# HW2.net
KiCad netlist of a schematic drawn in EAGLE
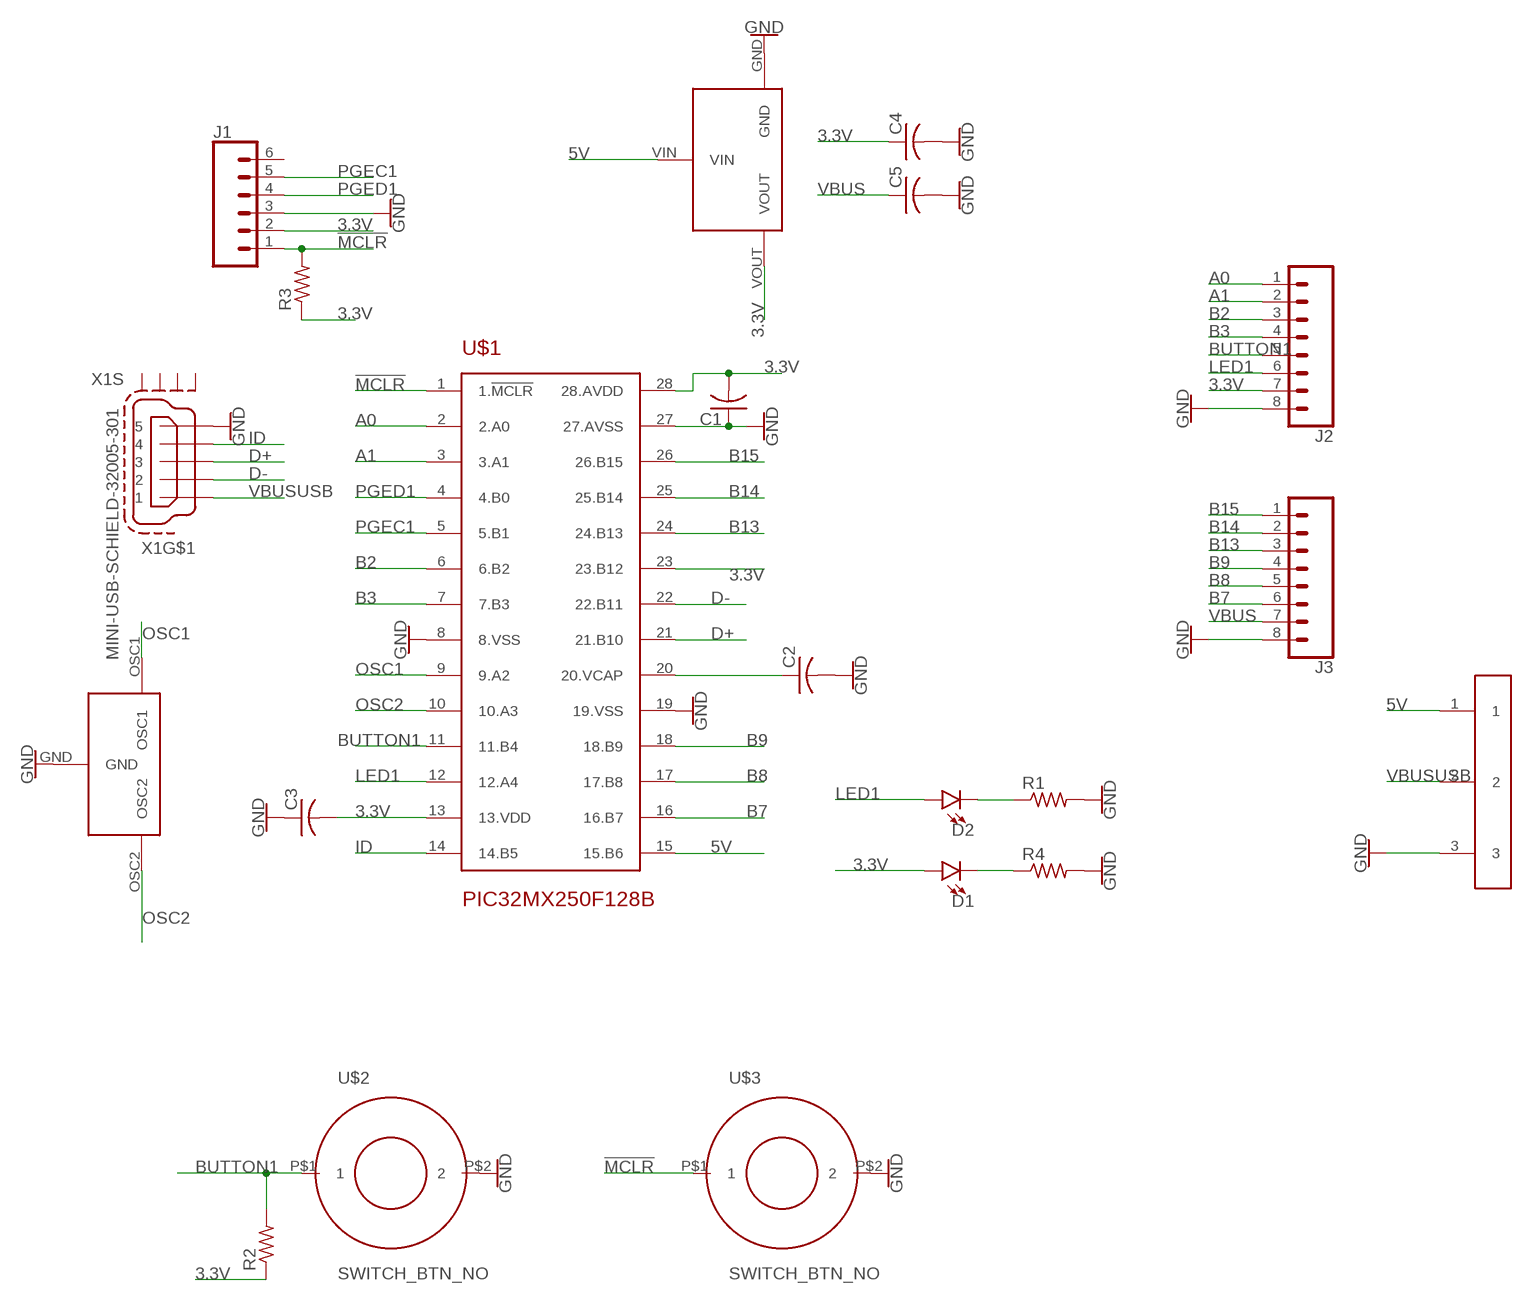
[diagram p0: schematic, sheet 1]

(export (version "E")
  (design (tool "Eeschema 10.0.6"))
  (components
    (comp (ref "C1")
      (value "C-US025-024X044")
      (footprint "eagle-import:C025-024X044")
      (libsource (lib "eagle-import") (part "C-US025-024X044"))
    )
    (comp (ref "C2")
      (value "C-US025-024X044")
      (footprint "eagle-import:C025-024X044")
      (libsource (lib "eagle-import") (part "C-US025-024X044"))
    )
    (comp (ref "C3")
      (value "C-US025-024X044")
      (footprint "eagle-import:C025-024X044")
      (libsource (lib "eagle-import") (part "C-US025-024X044"))
    )
    (comp (ref "C4")
      (value "C-US025-024X044")
      (footprint "eagle-import:C025-024X044")
      (libsource (lib "eagle-import") (part "C-US025-024X044"))
    )
    (comp (ref "C5")
      (value "C-US025-024X044")
      (footprint "eagle-import:C025-024X044")
      (libsource (lib "eagle-import") (part "C-US025-024X044"))
    )
    (comp (ref "D1")
      (value "LED3MM")
      (footprint "eagle-import:LED_3MM")
      (libsource (lib "eagle-import") (part "LED3MM"))
    )
    (comp (ref "D2")
      (value "LED3MM")
      (footprint "eagle-import:LED_3MM")
      (libsource (lib "eagle-import") (part "LED3MM"))
    )
    (comp (ref "J1")
      (value "CONN_06SILK_FEMALE_PTH")
      (footprint "eagle-import:1X06")
      (libsource (lib "eagle-import") (part "CONN_06SILK_FEMALE_PTH"))
    )
    (comp (ref "J2")
      (value "CONN_08\"")
      (footprint "eagle-import:1X08")
      (libsource (lib "eagle-import") (part "CONN_08{dblquote}"))
    )
    (comp (ref "J3")
      (value "CONN_08\"")
      (footprint "eagle-import:1X08")
      (libsource (lib "eagle-import") (part "CONN_08{dblquote}"))
    )
    (comp (ref "R1")
      (value "R-US_0204/7")
      (footprint "eagle-import:0204_7")
      (libsource (lib "eagle-import") (part "R-US_0204/7"))
    )
    (comp (ref "R2")
      (value "R-US_0204/7")
      (footprint "eagle-import:0204_7")
      (libsource (lib "eagle-import") (part "R-US_0204/7"))
    )
    (comp (ref "R3")
      (value "R-US_0204/7")
      (footprint "eagle-import:0204_7")
      (libsource (lib "eagle-import") (part "R-US_0204/7"))
    )
    (comp (ref "R4")
      (value "R-US_0204/7")
      (footprint "eagle-import:0204_7")
      (libsource (lib "eagle-import") (part "R-US_0204/7"))
    )
    (comp (ref "U$1")
      (value "PIC32MX250F128B")
      (footprint "eagle-import:DIL28-3")
      (libsource (lib "eagle-import") (part "PIC32MX250F128B"))
    )
    (comp (ref "U$2")
      (value "SWITCH_BTN_NO")
      (footprint "eagle-import:BTN_2")
      (libsource (lib "eagle-import") (part "SWITCH_BTN_NO"))
    )
    (comp (ref "U$3")
      (value "SWITCH_BTN_NO")
      (footprint "eagle-import:BTN_2")
      (libsource (lib "eagle-import") (part "SWITCH_BTN_NO"))
    )
    (comp (ref "U$4")
      (value "RESONATOR")
      (footprint "eagle-import:1X3")
      (libsource (lib "eagle-import") (part "RESONATOR"))
    )
    (comp (ref "U$5")
      (value "VREG3_3V")
      (footprint "eagle-import:1X3_VREG")
      (libsource (lib "eagle-import") (part "VREG3_3V"))
    )
    (comp (ref "U$6")
      (value "SLIDESWITCH")
      (footprint "eagle-import:SWITCH")
      (libsource (lib "eagle-import") (part "SLIDESWITCH"))
    )
    (comp (ref "X1")
      (value "MINI-USB-SCHIELD-32005-301")
      (footprint "eagle-import:32005-301")
      (libsource (lib "eagle-import") (part "MINI-USB-SCHIELD-32005-301"))
    )
  )
  (nets
    (net (code "1") (name "/3.3V") (class "Default")
      (node (ref "C1") (pin "2") (pinfunction "2_2") (pintype "passive"))
      (node (ref "C3") (pin "2") (pinfunction "2_2") (pintype "passive"))
      (node (ref "C4") (pin "1") (pinfunction "1_1") (pintype "passive"))
      (node (ref "D1") (pin "A") (pinfunction "A_A") (pintype "passive"))
      (node (ref "J1") (pin "2") (pinfunction "2_2") (pintype "passive"))
      (node (ref "J2") (pin "7") (pinfunction "7_7") (pintype "passive"))
      (node (ref "R2") (pin "1") (pinfunction "1_1") (pintype "passive"))
      (node (ref "R3") (pin "1") (pinfunction "1_1") (pintype "passive"))
      (node (ref "U$1") (pin "13") (pinfunction "13.VDD_13") (pintype "bidirectional"))
      (node (ref "U$1") (pin "23") (pinfunction "23.B12_23") (pintype "bidirectional"))
      (node (ref "U$1") (pin "28") (pinfunction "28.AVDD_28") (pintype "bidirectional"))
      (node (ref "U$5") (pin "VOUT") (pinfunction "VOUT_VOUT") (pintype "bidirectional"))
    )
    (net (code "2") (name "/5V") (class "Default")
      (node (ref "U$1") (pin "15") (pinfunction "15.B6_15") (pintype "bidirectional"))
      (node (ref "U$5") (pin "VIN") (pinfunction "VIN_VIN") (pintype "bidirectional"))
      (node (ref "U$6") (pin "1") (pinfunction "1_1") (pintype "bidirectional"))
    )
    (net (code "3") (name "/A0") (class "Default")
      (node (ref "J2") (pin "1") (pinfunction "1_1") (pintype "passive"))
      (node (ref "U$1") (pin "2") (pinfunction "2.A0_2") (pintype "bidirectional"))
    )
    (net (code "4") (name "/A1") (class "Default")
      (node (ref "J2") (pin "2") (pinfunction "2_2") (pintype "passive"))
      (node (ref "U$1") (pin "3") (pinfunction "3.A1_3") (pintype "bidirectional"))
    )
    (net (code "5") (name "/B2") (class "Default")
      (node (ref "J2") (pin "3") (pinfunction "3_3") (pintype "passive"))
      (node (ref "U$1") (pin "6") (pinfunction "6.B2_6") (pintype "bidirectional"))
    )
    (net (code "6") (name "/B3") (class "Default")
      (node (ref "J2") (pin "4") (pinfunction "4_4") (pintype "passive"))
      (node (ref "U$1") (pin "7") (pinfunction "7.B3_7") (pintype "bidirectional"))
    )
    (net (code "7") (name "/B7") (class "Default")
      (node (ref "J3") (pin "6") (pinfunction "6_6") (pintype "passive"))
      (node (ref "U$1") (pin "16") (pinfunction "16.B7_16") (pintype "bidirectional"))
    )
    (net (code "8") (name "/B8") (class "Default")
      (node (ref "J3") (pin "5") (pinfunction "5_5") (pintype "passive"))
      (node (ref "U$1") (pin "17") (pinfunction "17.B8_17") (pintype "bidirectional"))
    )
    (net (code "9") (name "/B9") (class "Default")
      (node (ref "J3") (pin "4") (pinfunction "4_4") (pintype "passive"))
      (node (ref "U$1") (pin "18") (pinfunction "18.B9_18") (pintype "bidirectional"))
    )
    (net (code "10") (name "/B13") (class "Default")
      (node (ref "J3") (pin "3") (pinfunction "3_3") (pintype "passive"))
      (node (ref "U$1") (pin "24") (pinfunction "24.B13_24") (pintype "bidirectional"))
    )
    (net (code "11") (name "/B14") (class "Default")
      (node (ref "J3") (pin "2") (pinfunction "2_2") (pintype "passive"))
      (node (ref "U$1") (pin "25") (pinfunction "25.B14_25") (pintype "bidirectional"))
    )
    (net (code "12") (name "/B15") (class "Default")
      (node (ref "J3") (pin "1") (pinfunction "1_1") (pintype "passive"))
      (node (ref "U$1") (pin "26") (pinfunction "26.B15_26") (pintype "bidirectional"))
    )
    (net (code "13") (name "/BUTTON1") (class "Default")
      (node (ref "J2") (pin "5") (pinfunction "5_5") (pintype "passive"))
      (node (ref "R2") (pin "2") (pinfunction "2_2") (pintype "passive"))
      (node (ref "U$1") (pin "11") (pinfunction "11.B4_11") (pintype "bidirectional"))
      (node (ref "U$2") (pin "P$1") (pinfunction "1_P$1") (pintype "bidirectional"))
    )
    (net (code "14") (name "/D+") (class "Default")
      (node (ref "U$1") (pin "21") (pinfunction "21.B10_21") (pintype "bidirectional"))
      (node (ref "X1") (pin "3") (pinfunction "3_3") (pintype "passive"))
    )
    (net (code "15") (name "/D-") (class "Default")
      (node (ref "U$1") (pin "22") (pinfunction "22.B11_22") (pintype "bidirectional"))
      (node (ref "X1") (pin "2") (pinfunction "2_2") (pintype "passive"))
    )
    (net (code "16") (name "/ID") (class "Default")
      (node (ref "U$1") (pin "14") (pinfunction "14.B5_14") (pintype "bidirectional"))
      (node (ref "X1") (pin "4") (pinfunction "4_4") (pintype "passive"))
    )
    (net (code "17") (name "/LED1") (class "Default")
      (node (ref "D2") (pin "A") (pinfunction "A_A") (pintype "passive"))
      (node (ref "J2") (pin "6") (pinfunction "6_6") (pintype "passive"))
      (node (ref "U$1") (pin "12") (pinfunction "12.A4_12") (pintype "bidirectional"))
    )
    (net (code "18") (name "/OSC1") (class "Default")
      (node (ref "U$1") (pin "9") (pinfunction "9.A2_9") (pintype "bidirectional"))
      (node (ref "U$4") (pin "OSC1") (pinfunction "OSC1_OSC1") (pintype "bidirectional"))
    )
    (net (code "19") (name "/OSC2") (class "Default")
      (node (ref "U$1") (pin "10") (pinfunction "10.A3_10") (pintype "bidirectional"))
      (node (ref "U$4") (pin "OSC2") (pinfunction "OSC2_OSC2") (pintype "bidirectional"))
    )
    (net (code "20") (name "/PGEC1") (class "Default")
      (node (ref "J1") (pin "5") (pinfunction "5_5") (pintype "passive"))
      (node (ref "U$1") (pin "5") (pinfunction "5.B1_5") (pintype "bidirectional"))
    )
    (net (code "21") (name "/PGED1") (class "Default")
      (node (ref "J1") (pin "4") (pinfunction "4_4") (pintype "passive"))
      (node (ref "U$1") (pin "4") (pinfunction "4.B0_4") (pintype "bidirectional"))
    )
    (net (code "22") (name "/VBUS") (class "Default")
      (node (ref "C5") (pin "1") (pinfunction "1_1") (pintype "passive"))
      (node (ref "J3") (pin "7") (pinfunction "7_7") (pintype "passive"))
    )
    (net (code "23") (name "/VBUSUSB") (class "Default")
      (node (ref "U$6") (pin "2") (pinfunction "2_2") (pintype "bidirectional"))
      (node (ref "X1") (pin "1") (pinfunction "1_1") (pintype "passive"))
    )
    (net (code "24") (name "/~{MCLR}") (class "Default")
      (node (ref "J1") (pin "1") (pinfunction "1_1") (pintype "passive"))
      (node (ref "R3") (pin "2") (pinfunction "2_2") (pintype "passive"))
      (node (ref "U$1") (pin "1") (pinfunction "1.~{MCLR}_1") (pintype "bidirectional"))
      (node (ref "U$3") (pin "P$1") (pinfunction "1_P$1") (pintype "bidirectional"))
    )
    (net (code "25") (name "GND") (class "Default")
      (node (ref "C1") (pin "1") (pinfunction "1_1") (pintype "passive"))
      (node (ref "C2") (pin "2") (pinfunction "2_2") (pintype "passive"))
      (node (ref "C3") (pin "1") (pinfunction "1_1") (pintype "passive"))
      (node (ref "C4") (pin "2") (pinfunction "2_2") (pintype "passive"))
      (node (ref "C5") (pin "2") (pinfunction "2_2") (pintype "passive"))
      (node (ref "J1") (pin "3") (pinfunction "3_3") (pintype "passive"))
      (node (ref "J2") (pin "8") (pinfunction "8_8") (pintype "passive"))
      (node (ref "J3") (pin "8") (pinfunction "8_8") (pintype "passive"))
      (node (ref "R1") (pin "2") (pinfunction "2_2") (pintype "passive"))
      (node (ref "R4") (pin "2") (pinfunction "2_2") (pintype "passive"))
      (node (ref "U$1") (pin "19") (pinfunction "19.VSS_19") (pintype "bidirectional"))
      (node (ref "U$1") (pin "27") (pinfunction "27.AVSS_27") (pintype "bidirectional"))
      (node (ref "U$1") (pin "8") (pinfunction "8.VSS_8") (pintype "bidirectional"))
      (node (ref "U$2") (pin "P$2") (pinfunction "2_P$2") (pintype "bidirectional"))
      (node (ref "U$3") (pin "P$2") (pinfunction "2_P$2") (pintype "bidirectional"))
      (node (ref "U$4") (pin "GND") (pinfunction "GND_GND") (pintype "bidirectional"))
      (node (ref "U$5") (pin "GND") (pinfunction "GND_GND") (pintype "bidirectional"))
      (node (ref "U$6") (pin "3") (pinfunction "3_3") (pintype "bidirectional"))
      (node (ref "X1") (pin "5") (pinfunction "5_5") (pintype "passive"))
    )
    (net (code "26") (name "Net-(D1-C)") (class "Default")
      (node (ref "D1") (pin "K") (pinfunction "C_K") (pintype "passive"))
      (node (ref "R4") (pin "1") (pinfunction "1_1") (pintype "passive"))
    )
    (net (code "27") (name "Net-(D2-C)") (class "Default")
      (node (ref "D2") (pin "K") (pinfunction "C_K") (pintype "passive"))
      (node (ref "R1") (pin "1") (pinfunction "1_1") (pintype "passive"))
    )
    (net (code "28") (name "Net-(U$1-20.VCAP)") (class "Default")
      (node (ref "C2") (pin "1") (pinfunction "1_1") (pintype "passive"))
      (node (ref "U$1") (pin "20") (pinfunction "20.VCAP_20") (pintype "bidirectional"))
    )
    (net (code "29") (name "unconnected-(J1-Pad6)") (class "Default")
      (node (ref "J1") (pin "6") (pinfunction "6_6") (pintype "passive"))
    )
    (net (code "30") (name "unconnected-(X1B-S1-PadM1)") (class "Default")
      (node (ref "X1") (pin "M1") (pinfunction "S1_M1") (pintype "passive"))
    )
    (net (code "31") (name "unconnected-(X1B-S2-PadM2)") (class "Default")
      (node (ref "X1") (pin "M2") (pinfunction "S2_M2") (pintype "passive"))
    )
    (net (code "32") (name "unconnected-(X1B-S3-PadM3)") (class "Default")
      (node (ref "X1") (pin "M3") (pinfunction "S3_M3") (pintype "passive"))
    )
    (net (code "33") (name "unconnected-(X1B-S4-PadM4)") (class "Default")
      (node (ref "X1") (pin "M4") (pinfunction "S4_M4") (pintype "passive"))
    )
  )
)
